# SR.net
KiCad netlist of a schematic drawn in Altium Designer
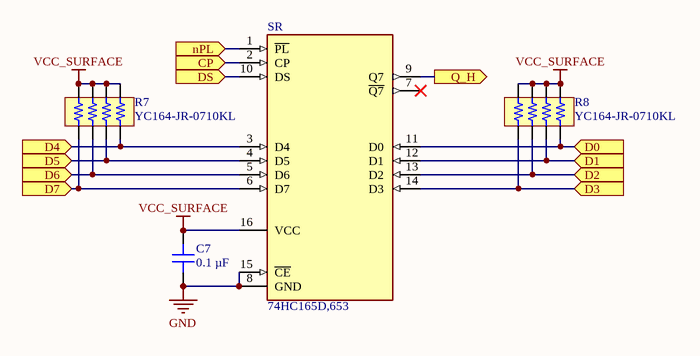
[diagram p0: SR.SchDoc]

(export (version "E")
  (design (tool "Eeschema 10.0.6"))
  (components
    (comp (ref "C7")
      (value "0.1 µF")
      (footprint "CAP 0603_1608")
      (description "CAP CER 0.1UF 16V X7R 0603")
      (fields (field (name "PART NUMBER") "CC0603KPX7R7BB104") (field (name "MANUFACTURER") "Yageo"))
      (libsource (lib "Celestial Altium Library - altium_library") (part "Capacitor"))
    )
    (comp (ref "R7")
      (value "YC164-JR-0710KL")
      (footprint "RESNET 1206-8 CONVEX")
      (description "RES ARRAY 4 RES 10K OHM 1206")
      (fields (field (name "MANUFACTURER") "Yageo") (field (name "TOLERANCE") "±5%"))
      (libsource (lib "Celestial Altium Library - altium_library") (part "Resistor Array (4 circuit)"))
    )
    (comp (ref "R8")
      (value "YC164-JR-0710KL")
      (footprint "RESNET 1206-8 CONVEX")
      (description "RES ARRAY 4 RES 10K OHM 1206")
      (fields (field (name "MANUFACTURER") "Yageo") (field (name "TOLERANCE") "±5%"))
      (libsource (lib "Celestial Altium Library - altium_library") (part "Resistor Array (4 circuit)"))
    )
    (comp (ref "SR")
      (value "74HC165D,653")
      (footprint "FP-SOT109-1-MFG")
      (description "IC SHIFT REGST 8BIT PI-SO 16SOIC")
      (fields
        (field (name "MANUFACTURER") "Nexperia")
        (field (name "OCTOPART") "https://octopart.com/74hc165d%2C653-nexperia-78737091")
      )
      (libsource (lib "Altium Content Vault") (part "62206be407dde36a55674a9f8997e2d"))
    )
  )
  (nets
    (net (code "1") (name "/CP") (class "Default")
      (node (ref "SR") (pin "2") (pinfunction "CP_2") (pintype "input"))
    )
    (net (code "2") (name "/D0") (class "Default")
      (node (ref "R8") (pin "4") (pinfunction "4_4") (pintype "passive"))
      (node (ref "SR") (pin "11") (pinfunction "D0_11") (pintype "input"))
    )
    (net (code "3") (name "/D1") (class "Default")
      (node (ref "R8") (pin "3") (pinfunction "3_3") (pintype "passive"))
      (node (ref "SR") (pin "12") (pinfunction "D1_12") (pintype "input"))
    )
    (net (code "4") (name "/D2") (class "Default")
      (node (ref "R8") (pin "2") (pinfunction "2_2") (pintype "passive"))
      (node (ref "SR") (pin "13") (pinfunction "D2_13") (pintype "input"))
    )
    (net (code "5") (name "/D3") (class "Default")
      (node (ref "R8") (pin "1") (pinfunction "1_1") (pintype "passive"))
      (node (ref "SR") (pin "14") (pinfunction "D3_14") (pintype "input"))
    )
    (net (code "6") (name "/D4") (class "Default")
      (node (ref "R7") (pin "4") (pinfunction "4_4") (pintype "passive"))
      (node (ref "SR") (pin "3") (pinfunction "D4_3") (pintype "input"))
    )
    (net (code "7") (name "/D5") (class "Default")
      (node (ref "R7") (pin "3") (pinfunction "3_3") (pintype "passive"))
      (node (ref "SR") (pin "4") (pinfunction "D5_4") (pintype "input"))
    )
    (net (code "8") (name "/D6") (class "Default")
      (node (ref "R7") (pin "2") (pinfunction "2_2") (pintype "passive"))
      (node (ref "SR") (pin "5") (pinfunction "D6_5") (pintype "input"))
    )
    (net (code "9") (name "/D7") (class "Default")
      (node (ref "R7") (pin "1") (pinfunction "1_1") (pintype "passive"))
      (node (ref "SR") (pin "6") (pinfunction "D7_6") (pintype "input"))
    )
    (net (code "10") (name "/DS") (class "Default")
      (node (ref "SR") (pin "10") (pinfunction "DS_10") (pintype "input"))
    )
    (net (code "11") (name "/Q_H") (class "Default")
      (node (ref "SR") (pin "9") (pinfunction "Q7_9") (pintype "output"))
    )
    (net (code "12") (name "/nPL") (class "Default")
      (node (ref "SR") (pin "1") (pinfunction "~{PL}_1") (pintype "input"))
    )
    (net (code "13") (name "GND") (class "Default")
      (node (ref "C7") (pin "1") (pinfunction "1_1") (pintype "passive"))
      (node (ref "SR") (pin "15") (pinfunction "~{CE}_15") (pintype "input"))
      (node (ref "SR") (pin "8") (pinfunction "GND_8") (pintype "power_in"))
    )
    (net (code "14") (name "VCC_SURFACE") (class "Default")
      (node (ref "C7") (pin "2") (pinfunction "2_2") (pintype "passive"))
      (node (ref "R7") (pin "5") (pinfunction "5_5") (pintype "passive"))
      (node (ref "R7") (pin "6") (pinfunction "6_6") (pintype "passive"))
      (node (ref "R7") (pin "7") (pinfunction "7_7") (pintype "passive"))
      (node (ref "R7") (pin "8") (pinfunction "8_8") (pintype "passive"))
      (node (ref "R8") (pin "5") (pinfunction "5_5") (pintype "passive"))
      (node (ref "R8") (pin "6") (pinfunction "6_6") (pintype "passive"))
      (node (ref "R8") (pin "7") (pinfunction "7_7") (pintype "passive"))
      (node (ref "R8") (pin "8") (pinfunction "8_8") (pintype "passive"))
      (node (ref "SR") (pin "16") (pinfunction "VCC_16") (pintype "power_in"))
    )
    (net (code "15") (name "unconnected-(SR-~{Q7}-Pad7)") (class "Default")
      (node (ref "SR") (pin "7") (pinfunction "~{Q7}_7") (pintype "output+no_connect"))
    )
  )
)
